# ICM-20948-Pico.net
KiCad netlist of a schematic drawn in EasyEDA Pro
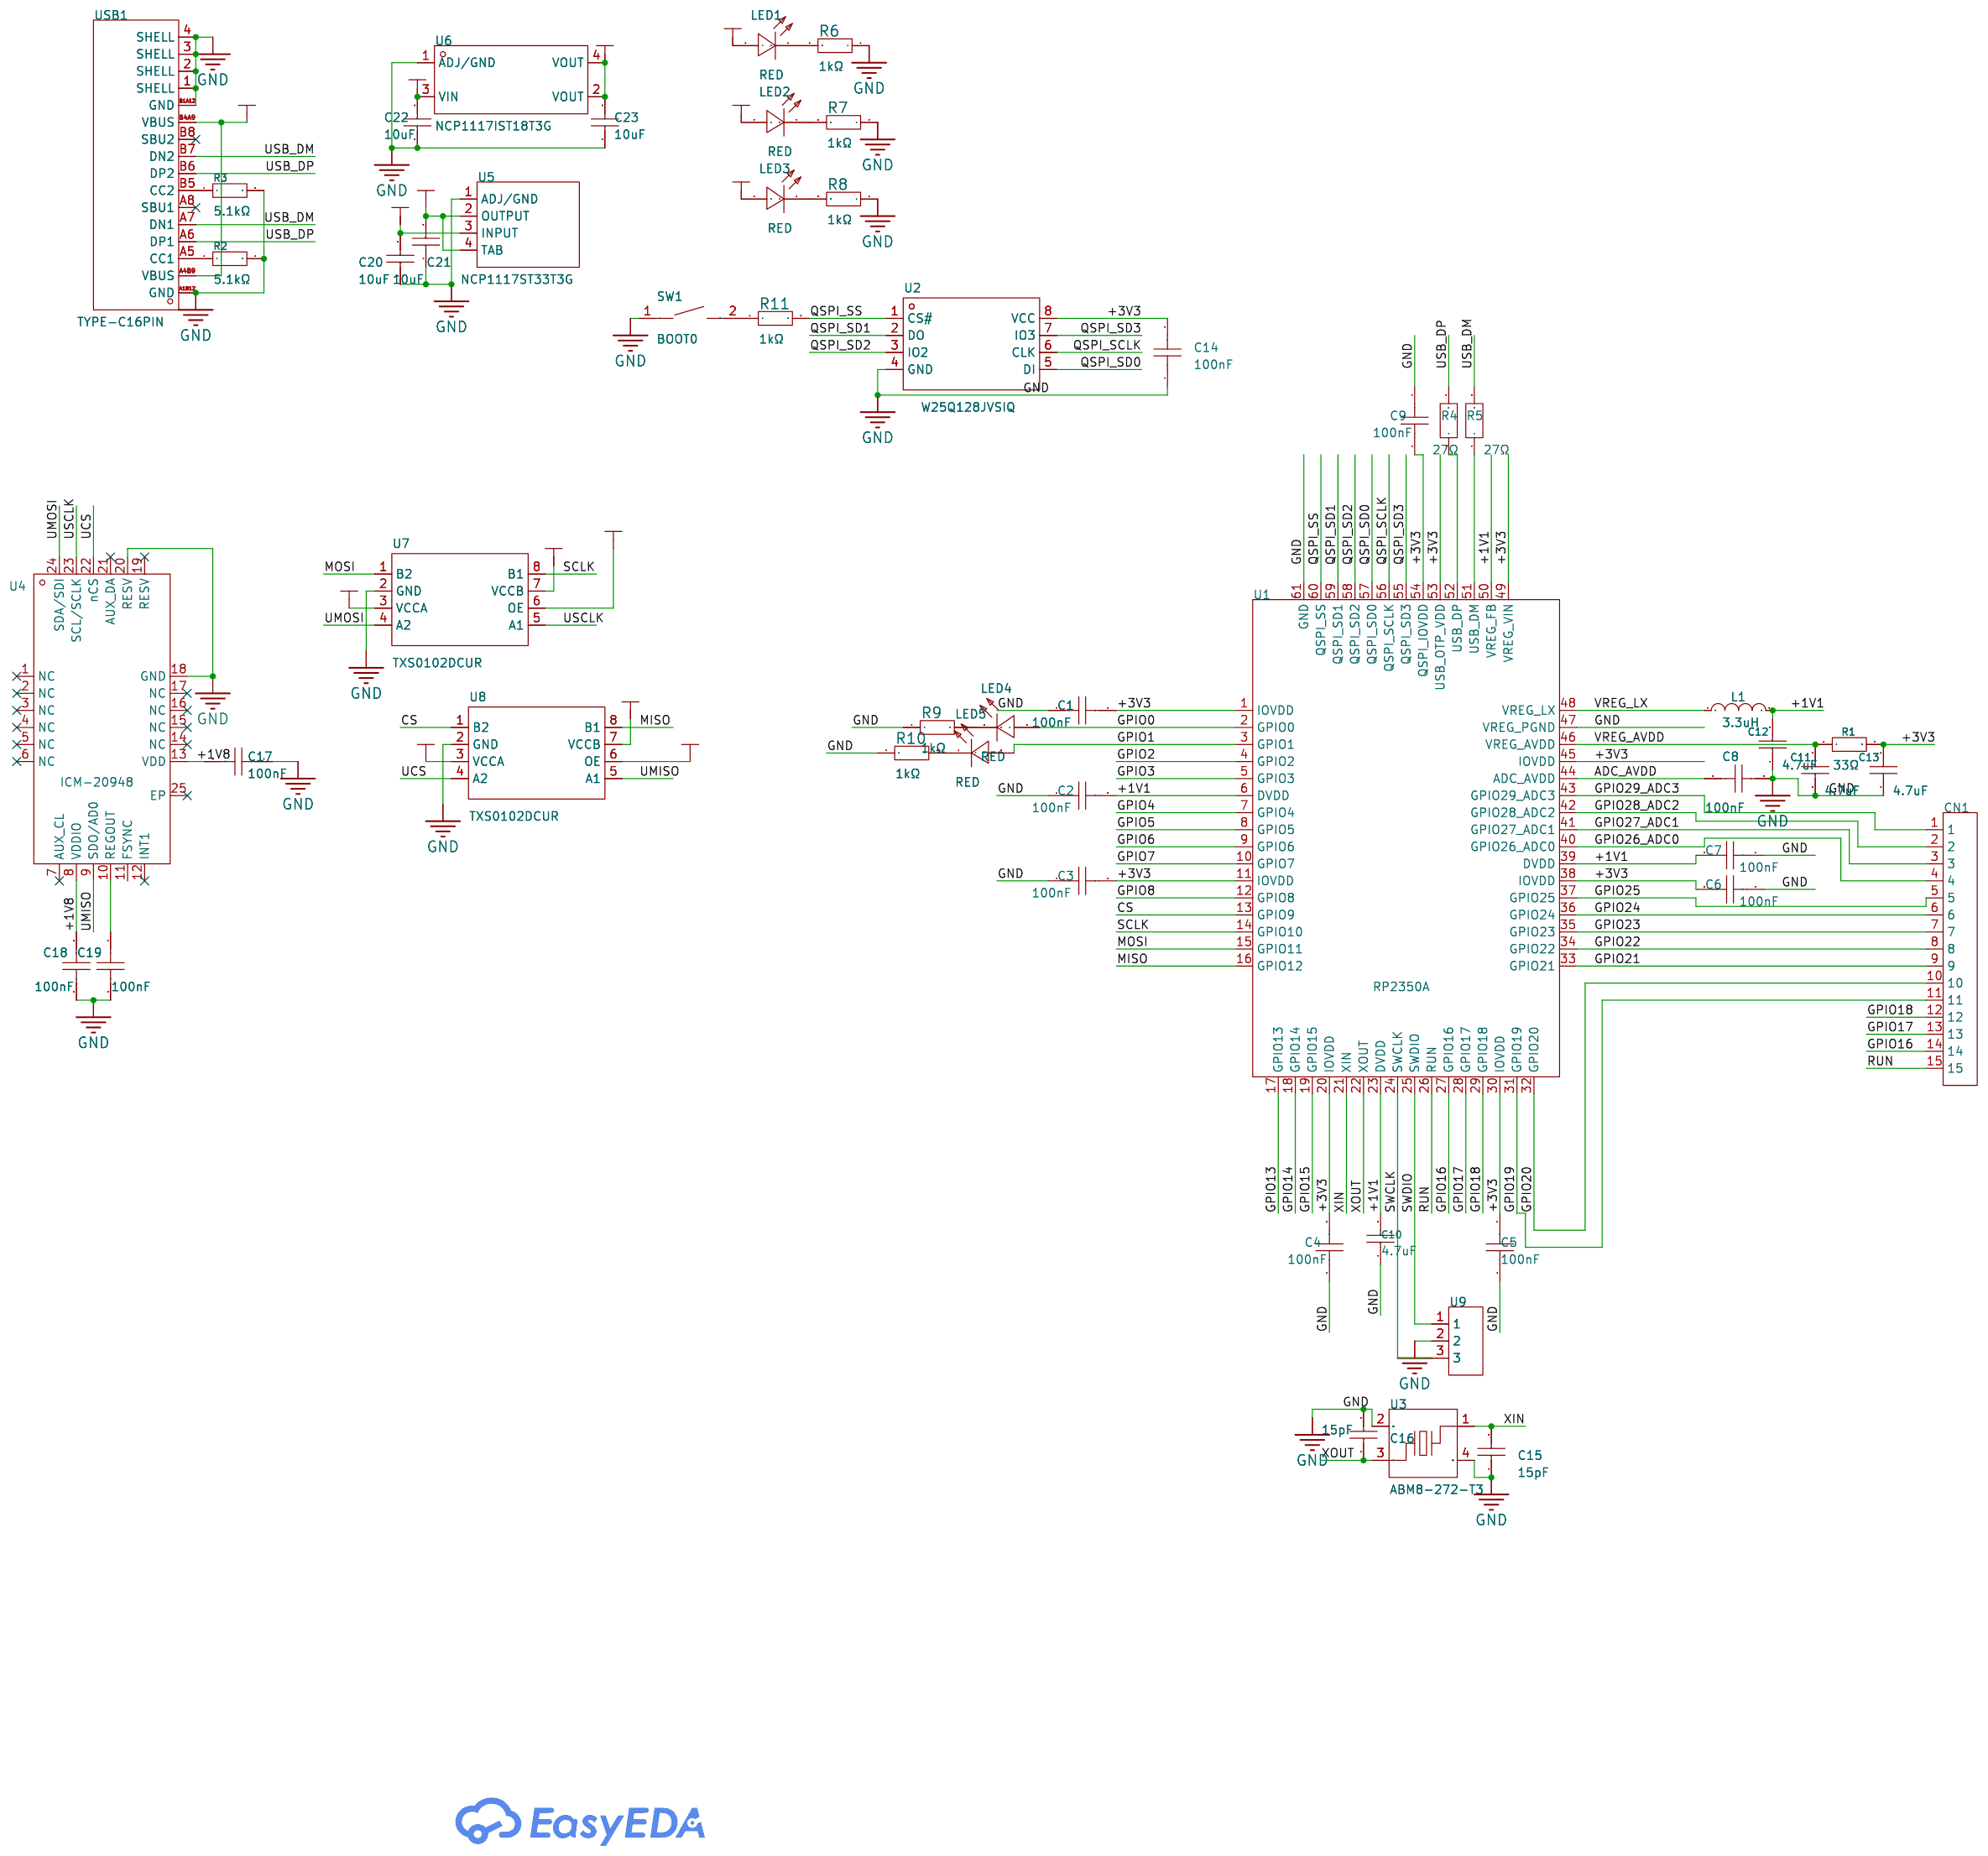
[diagram p0: schematic sheet]

(export (version "E")
  (design (tool "Eeschema 10.0.6"))
  (components
    (comp (ref "C1")
      (value "100nF")
      (footprint "easyedapro:C0402")
      (fields
        (field (name "Manufacturer Part") "CL05B104KO5NNNC")
        (field (name "Manufacturer") "SAMSUNG(三星)")
      )
      (libsource (lib "easyedapro") (part "CL05B104KO5NNNC"))
    )
    (comp (ref "C2")
      (value "100nF")
      (footprint "easyedapro:C0402")
      (fields
        (field (name "Manufacturer Part") "CL05B104KO5NNNC")
        (field (name "Manufacturer") "SAMSUNG(三星)")
      )
      (libsource (lib "easyedapro") (part "CL05B104KO5NNNC"))
    )
    (comp (ref "C3")
      (value "100nF")
      (footprint "easyedapro:C0402")
      (fields
        (field (name "Manufacturer Part") "CL05B104KO5NNNC")
        (field (name "Manufacturer") "SAMSUNG(三星)")
      )
      (libsource (lib "easyedapro") (part "CL05B104KO5NNNC"))
    )
    (comp (ref "C4")
      (value "100nF")
      (footprint "easyedapro:C0402")
      (fields
        (field (name "Manufacturer Part") "CL05B104KO5NNNC")
        (field (name "Manufacturer") "SAMSUNG(三星)")
      )
      (libsource (lib "easyedapro") (part "CL05B104KO5NNNC"))
    )
    (comp (ref "C5")
      (value "100nF")
      (footprint "easyedapro:C0402")
      (fields
        (field (name "Manufacturer Part") "CL05B104KO5NNNC")
        (field (name "Manufacturer") "SAMSUNG(三星)")
      )
      (libsource (lib "easyedapro") (part "CL05B104KO5NNNC"))
    )
    (comp (ref "C6")
      (value "100nF")
      (footprint "easyedapro:C0402")
      (fields
        (field (name "Manufacturer Part") "CL05B104KO5NNNC")
        (field (name "Manufacturer") "SAMSUNG(三星)")
      )
      (libsource (lib "easyedapro") (part "CL05B104KO5NNNC"))
    )
    (comp (ref "C7")
      (value "100nF")
      (footprint "easyedapro:C0402")
      (fields
        (field (name "Manufacturer Part") "CL05B104KO5NNNC")
        (field (name "Manufacturer") "SAMSUNG(三星)")
      )
      (libsource (lib "easyedapro") (part "CL05B104KO5NNNC"))
    )
    (comp (ref "C8")
      (value "100nF")
      (footprint "easyedapro:C0402")
      (fields
        (field (name "Manufacturer Part") "CL05B104KO5NNNC")
        (field (name "Manufacturer") "SAMSUNG(三星)")
      )
      (libsource (lib "easyedapro") (part "CL05B104KO5NNNC"))
    )
    (comp (ref "C9")
      (value "100nF")
      (footprint "easyedapro:C0402")
      (fields
        (field (name "Manufacturer Part") "CL05B104KO5NNNC")
        (field (name "Manufacturer") "SAMSUNG(三星)")
      )
      (libsource (lib "easyedapro") (part "CL05B104KO5NNNC"))
    )
    (comp (ref "C10")
      (value "4.7uF")
      (footprint "easyedapro:C0402")
      (fields
        (field (name "Manufacturer Part") "CL05A475MP5NRNC")
        (field (name "Manufacturer") "SAMSUNG(三星)")
      )
      (libsource (lib "easyedapro") (part "CL05A475MP5NRNC"))
    )
    (comp (ref "C11")
      (value "4.7uF")
      (footprint "easyedapro:C0402")
      (fields
        (field (name "Manufacturer Part") "CL05A475MP5NRNC")
        (field (name "Manufacturer") "SAMSUNG(三星)")
      )
      (libsource (lib "easyedapro") (part "CL05A475MP5NRNC"))
    )
    (comp (ref "C12")
      (value "4.7uF")
      (footprint "easyedapro:C0402")
      (fields
        (field (name "Manufacturer Part") "CL05A475MP5NRNC")
        (field (name "Manufacturer") "SAMSUNG(三星)")
      )
      (libsource (lib "easyedapro") (part "CL05A475MP5NRNC"))
    )
    (comp (ref "C13")
      (value "4.7uF")
      (footprint "easyedapro:C0402")
      (fields
        (field (name "Manufacturer Part") "CL05A475MP5NRNC")
        (field (name "Manufacturer") "SAMSUNG(三星)")
      )
      (libsource (lib "easyedapro") (part "CL05A475MP5NRNC"))
    )
    (comp (ref "C14")
      (value "100nF")
      (footprint "easyedapro:C0402")
      (fields
        (field (name "Manufacturer Part") "CL05B104KO5NNNC")
        (field (name "Manufacturer") "SAMSUNG(三星)")
      )
      (libsource (lib "easyedapro") (part "CL05B104KO5NNNC"))
    )
    (comp (ref "C15")
      (value "15pF")
      (footprint "easyedapro:C0402")
      (fields (field (name "Manufacturer Part") "0402CG150J500NT") (field (name "Manufacturer") "FH(风华)"))
      (libsource (lib "easyedapro") (part "0402CG150J500NT"))
    )
    (comp (ref "C16")
      (value "15pF")
      (footprint "easyedapro:C0402")
      (fields (field (name "Manufacturer Part") "0402CG150J500NT") (field (name "Manufacturer") "FH(风华)"))
      (libsource (lib "easyedapro") (part "0402CG150J500NT"))
    )
    (comp (ref "C17")
      (value "100nF")
      (footprint "easyedapro:C0402")
      (fields
        (field (name "Manufacturer Part") "CL05B104KO5NNNC")
        (field (name "Manufacturer") "SAMSUNG(三星)")
      )
      (libsource (lib "easyedapro") (part "CL05B104KO5NNNC"))
    )
    (comp (ref "C18")
      (value "100nF")
      (footprint "easyedapro:C0402")
      (fields
        (field (name "Manufacturer Part") "CL05B104KO5NNNC")
        (field (name "Manufacturer") "SAMSUNG(三星)")
      )
      (libsource (lib "easyedapro") (part "CL05B104KO5NNNC"))
    )
    (comp (ref "C19")
      (value "100nF")
      (footprint "easyedapro:C0402")
      (fields
        (field (name "Manufacturer Part") "CL05B104KO5NNNC")
        (field (name "Manufacturer") "SAMSUNG(三星)")
      )
      (libsource (lib "easyedapro") (part "CL05B104KO5NNNC"))
    )
    (comp (ref "C20")
      (value "10uF")
      (footprint "easyedapro:C0402")
      (fields
        (field (name "Manufacturer Part") "CL05A106MQ5NUNC")
        (field (name "Manufacturer") "SAMSUNG(三星)")
      )
      (libsource (lib "easyedapro") (part "CL05A106MQ5NUNC"))
    )
    (comp (ref "C21")
      (value "10uF")
      (footprint "easyedapro:C0402")
      (fields
        (field (name "Manufacturer Part") "CL05A106MQ5NUNC")
        (field (name "Manufacturer") "SAMSUNG(三星)")
      )
      (libsource (lib "easyedapro") (part "CL05A106MQ5NUNC"))
    )
    (comp (ref "C22")
      (value "10uF")
      (footprint "easyedapro:C0402")
      (fields
        (field (name "Manufacturer Part") "CL05A106MQ5NUNC")
        (field (name "Manufacturer") "SAMSUNG(三星)")
      )
      (libsource (lib "easyedapro") (part "CL05A106MQ5NUNC"))
    )
    (comp (ref "C23")
      (value "10uF")
      (footprint "easyedapro:C0402")
      (fields
        (field (name "Manufacturer Part") "CL05A106MQ5NUNC")
        (field (name "Manufacturer") "SAMSUNG(三星)")
      )
      (libsource (lib "easyedapro") (part "CL05A106MQ5NUNC"))
    )
    (comp (ref "CN1")
      (value "排母插针1X15P")
      (footprint "easyedapro:CONN-TH_15P-L38.5-W2.4-P2.54")
      (libsource (lib "easyedapro") (part "排母插针1X15P"))
    )
    (comp (ref "L1")
      (value "3.3uH")
      (footprint "easyedapro:IND-SMD_L2.0-W1.6_AOTA-B201610S3R3-101-T")
      (fields (field (name "Manufacturer") "ABRACON"))
      (libsource (lib "easyedapro") (part "AOTA-B201610S3R3-101-T"))
    )
    (comp (ref "LED1")
      (value "RED")
      (footprint "easyedapro:LED0603-RD")
      (fields (field (name "Manufacturer") "KENTO"))
      (libsource (lib "easyedapro") (part "KT-0603R"))
    )
    (comp (ref "LED2")
      (value "RED")
      (footprint "easyedapro:LED0603-RD")
      (fields (field (name "Manufacturer") "KENTO"))
      (libsource (lib "easyedapro") (part "KT-0603R"))
    )
    (comp (ref "LED3")
      (value "RED")
      (footprint "easyedapro:LED0603-RD")
      (fields (field (name "Manufacturer") "KENTO"))
      (libsource (lib "easyedapro") (part "KT-0603R"))
    )
    (comp (ref "LED4")
      (value "RED")
      (footprint "easyedapro:LED0603-RD")
      (fields (field (name "Manufacturer") "KENTO"))
      (libsource (lib "easyedapro") (part "KT-0603R"))
    )
    (comp (ref "LED5")
      (value "RED")
      (footprint "easyedapro:LED0603-RD")
      (fields (field (name "Manufacturer") "KENTO"))
      (libsource (lib "easyedapro") (part "KT-0603R"))
    )
    (comp (ref "R1")
      (value "33Ω")
      (footprint "easyedapro:R0402")
      (fields
        (field (name "Manufacturer Part") "0402WGF330JTCE")
        (field (name "Manufacturer") "UNI-ROYAL(厚声)")
      )
      (libsource (lib "easyedapro") (part "0402WGF330JTCE"))
    )
    (comp (ref "R2")
      (value "5.1kΩ")
      (footprint "easyedapro:R0402")
      (fields
        (field (name "Manufacturer Part") "0402WGF5101TCE")
        (field (name "Manufacturer") "UNI-ROYAL(厚声)")
      )
      (libsource (lib "easyedapro") (part "0402WGF5101TCE"))
    )
    (comp (ref "R3")
      (value "5.1kΩ")
      (footprint "easyedapro:R0402")
      (fields
        (field (name "Manufacturer Part") "0402WGF5101TCE")
        (field (name "Manufacturer") "UNI-ROYAL(厚声)")
      )
      (libsource (lib "easyedapro") (part "0402WGF5101TCE"))
    )
    (comp (ref "R4")
      (value "27Ω")
      (footprint "easyedapro:R0402")
      (fields (field (name "Manufacturer Part") "WR04X270JTL") (field (name "Manufacturer") "Walsin(华新科)"))
      (libsource (lib "easyedapro") (part "WR04X270 JTL"))
    )
    (comp (ref "R5")
      (value "27Ω")
      (footprint "easyedapro:R0402")
      (fields (field (name "Manufacturer Part") "WR04X270JTL") (field (name "Manufacturer") "Walsin(华新科)"))
      (libsource (lib "easyedapro") (part "WR04X270 JTL"))
    )
    (comp (ref "R6")
      (value "1kΩ")
      (footprint "easyedapro:R0402")
      (fields
        (field (name "Manufacturer Part") "0402WGF1001TCE")
        (field (name "Manufacturer") "UNI-ROYAL(厚声)")
      )
      (libsource (lib "easyedapro") (part "0402WGF1001TCE"))
    )
    (comp (ref "R7")
      (value "1kΩ")
      (footprint "easyedapro:R0402")
      (fields
        (field (name "Manufacturer Part") "0402WGF1001TCE")
        (field (name "Manufacturer") "UNI-ROYAL(厚声)")
      )
      (libsource (lib "easyedapro") (part "0402WGF1001TCE"))
    )
    (comp (ref "R8")
      (value "1kΩ")
      (footprint "easyedapro:R0402")
      (fields
        (field (name "Manufacturer Part") "0402WGF1001TCE")
        (field (name "Manufacturer") "UNI-ROYAL(厚声)")
      )
      (libsource (lib "easyedapro") (part "0402WGF1001TCE"))
    )
    (comp (ref "R9")
      (value "1kΩ")
      (footprint "easyedapro:R0402")
      (fields
        (field (name "Manufacturer Part") "0402WGF1001TCE")
        (field (name "Manufacturer") "UNI-ROYAL(厚声)")
      )
      (libsource (lib "easyedapro") (part "0402WGF1001TCE"))
    )
    (comp (ref "R10")
      (value "1kΩ")
      (footprint "easyedapro:R0402")
      (fields
        (field (name "Manufacturer Part") "0402WGF1001TCE")
        (field (name "Manufacturer") "UNI-ROYAL(厚声)")
      )
      (libsource (lib "easyedapro") (part "0402WGF1001TCE"))
    )
    (comp (ref "R11")
      (value "1kΩ")
      (footprint "easyedapro:R0402")
      (fields
        (field (name "Manufacturer Part") "0402WGF1001TCE")
        (field (name "Manufacturer") "UNI-ROYAL(厚声)")
      )
      (libsource (lib "easyedapro") (part "0402WGF1001TCE"))
    )
    (comp (ref "SW1")
      (value "BOOT0")
      (footprint "easyedapro:SW-SMD_L3.9-W3.0-P4.45")
      (fields (field (name "Manufacturer") "XUNPU(讯普)"))
      (libsource (lib "easyedapro") (part "TS-1088-AR02016"))
    )
    (comp (ref "U1")
      (value "RP2350A")
      (footprint "easyedapro:QFN-60_L7.0-W7.0-P0.40-TL-EP3.4")
      (fields (field (name "Manufacturer") "Raspberry Pi(树莓派)"))
      (libsource (lib "easyedapro") (part "RP2350A_C42411118"))
    )
    (comp (ref "U2")
      (value "W25Q128JVSIQ")
      (footprint "easyedapro:SOIC-8_L5.3-W5.3-P1.27-LS8.0-BL")
      (fields (field (name "Manufacturer") "WINBOND(华邦)"))
      (libsource (lib "easyedapro") (part "W25Q128JVSIQTR"))
    )
    (comp (ref "U3")
      (value "ABM8-272-T3")
      (footprint "easyedapro:CRYSTAL-SMD_4P-L3.2-W2.5-BL")
      (fields (field (name "Manufacturer") "ABRACON"))
      (libsource (lib "easyedapro") (part "ABM8-272-T3_C20625731"))
    )
    (comp (ref "U4")
      (value "ICM-20948")
      (footprint "easyedapro:QFN-24_L3.0-W3.0-P0.40-BL-EP")
      (fields (field (name "Manufacturer") "TDK InvenSense(应美盛)"))
      (libsource (lib "easyedapro") (part "ICM-20948"))
    )
    (comp (ref "U5")
      (value "NCP1117ST33T3G")
      (footprint "easyedapro:SOT-223-3_L6.5-W3.4-P2.30-LS7.0-BR")
      (fields (field (name "Manufacturer") "onsemi(安森美)"))
      (libsource (lib "easyedapro") (part "NCP1117ST33T3G"))
    )
    (comp (ref "U6")
      (value "NCP1117IST18T3G")
      (footprint "easyedapro:SOT-223_L6.5-W3.5-P2.30-LS7.0-BR")
      (fields (field (name "Manufacturer") "onsemi(安森美)"))
      (libsource (lib "easyedapro") (part "NCP1117IST18T3G"))
    )
    (comp (ref "U7")
      (value "TXS0102DCUR")
      (footprint "easyedapro:VSON8_L2.0-W2.3-P0.50-LS3.1-BL")
      (fields (field (name "Manufacturer") "TI(德州仪器)"))
      (libsource (lib "easyedapro") (part "TXS0102DCUR"))
    )
    (comp (ref "U8")
      (value "TXS0102DCUR")
      (footprint "easyedapro:VSON8_L2.0-W2.3-P0.50-LS3.1-BL")
      (fields (field (name "Manufacturer") "TI(德州仪器)"))
      (libsource (lib "easyedapro") (part "TXS0102DCUR"))
    )
    (comp (ref "U9")
      (value "HB-PH3-25413PB2GOP")
      (footprint "easyedapro:HDR-TH_3P-P2.54-V-M")
      (fields (field (name "Manufacturer") "HANBO(汉博)"))
      (libsource (lib "easyedapro") (part "HB-PH3-25413PB2GOP"))
    )
    (comp (ref "USB1")
      (value "TYPE-C16PIN")
      (footprint "easyedapro:USB-C-SMD_TYPE-C16PIN")
      (fields (field (name "Manufacturer") "SHOU HAN(首韩)"))
      (libsource (lib "easyedapro") (part "TYPE-C16PIN"))
    )
  )
  (nets
    (net (code "1") (name "+1V8") (class "Default")
      (node (ref "C17") (pin "2") (pinfunction "2_2") (pintype "unspecified"))
      (node (ref "C18") (pin "1") (pinfunction "1_1") (pintype "unspecified"))
      (node (ref "C23") (pin "2") (pinfunction "2_2") (pintype "input"))
      (node (ref "LED3") (pin "2") (pinfunction "A_2") (pintype "unspecified"))
      (node (ref "U4") (pin "13") (pinfunction "VDD_13") (pintype "unspecified"))
      (node (ref "U4") (pin "8") (pinfunction "VDDIO_8") (pintype "unspecified"))
      (node (ref "U6") (pin "2") (pinfunction "VOUT_2") (pintype "unspecified"))
      (node (ref "U6") (pin "4") (pinfunction "VOUT_4") (pintype "unspecified"))
      (node (ref "U7") (pin "3") (pinfunction "VCCA_3") (pintype "unspecified"))
      (node (ref "U7") (pin "6") (pinfunction "OE_6") (pintype "unspecified"))
      (node (ref "U8") (pin "3") (pinfunction "VCCA_3") (pintype "unspecified"))
      (node (ref "U8") (pin "6") (pinfunction "OE_6") (pintype "unspecified"))
    )
    (net (code "2") (name "+3V3") (class "Default")
      (node (ref "C1") (pin "2") (pinfunction "2_2") (pintype "unspecified"))
      (node (ref "C13") (pin "2") (pinfunction "2_2") (pintype "input"))
      (node (ref "C14") (pin "2") (pinfunction "2_2") (pintype "unspecified"))
      (node (ref "C21") (pin "2") (pinfunction "2_2") (pintype "input"))
      (node (ref "C3") (pin "2") (pinfunction "2_2") (pintype "unspecified"))
      (node (ref "C4") (pin "2") (pinfunction "2_2") (pintype "unspecified"))
      (node (ref "C5") (pin "2") (pinfunction "2_2") (pintype "unspecified"))
      (node (ref "C6") (pin "2") (pinfunction "2_2") (pintype "unspecified"))
      (node (ref "C9") (pin "2") (pinfunction "2_2") (pintype "unspecified"))
      (node (ref "LED2") (pin "2") (pinfunction "A_2") (pintype "unspecified"))
      (node (ref "R1") (pin "2") (pinfunction "2_2") (pintype "input"))
      (node (ref "U1") (pin "1") (pinfunction "IOVDD_1") (pintype "unspecified"))
      (node (ref "U1") (pin "11") (pinfunction "IOVDD_11") (pintype "unspecified"))
      (node (ref "U1") (pin "20") (pinfunction "IOVDD_20") (pintype "unspecified"))
      (node (ref "U1") (pin "30") (pinfunction "IOVDD_30") (pintype "unspecified"))
      (node (ref "U1") (pin "38") (pinfunction "IOVDD_38") (pintype "unspecified"))
      (node (ref "U1") (pin "45") (pinfunction "IOVDD_45") (pintype "unspecified"))
      (node (ref "U1") (pin "49") (pinfunction "VREG_VIN_49") (pintype "unspecified"))
      (node (ref "U1") (pin "53") (pinfunction "USB_OTP_VDD_53") (pintype "unspecified"))
      (node (ref "U1") (pin "54") (pinfunction "QSPI_IOVDD_54") (pintype "unspecified"))
      (node (ref "U2") (pin "8") (pinfunction "VCC_8") (pintype "unspecified"))
      (node (ref "U5") (pin "2") (pinfunction "OUTPUT_2") (pintype "unspecified"))
      (node (ref "U5") (pin "4") (pinfunction "TAB_4") (pintype "unspecified"))
      (node (ref "U7") (pin "7") (pinfunction "VCCB_7") (pintype "unspecified"))
      (node (ref "U8") (pin "7") (pinfunction "VCCB_7") (pintype "unspecified"))
    )
    (net (code "3") (name "/+1V1") (class "Default")
      (node (ref "C10") (pin "2") (pinfunction "2_2") (pintype "input"))
      (node (ref "C12") (pin "2") (pinfunction "2_2") (pintype "input"))
      (node (ref "C2") (pin "2") (pinfunction "2_2") (pintype "unspecified"))
      (node (ref "C7") (pin "2") (pinfunction "2_2") (pintype "unspecified"))
      (node (ref "L1") (pin "2") (pinfunction "2_2") (pintype "unspecified"))
      (node (ref "U1") (pin "23") (pinfunction "DVDD_23") (pintype "unspecified"))
      (node (ref "U1") (pin "39") (pinfunction "DVDD_39") (pintype "unspecified"))
      (node (ref "U1") (pin "50") (pinfunction "VREG_FB_50") (pintype "unspecified"))
      (node (ref "U1") (pin "6") (pinfunction "DVDD_6") (pintype "unspecified"))
    )
    (net (code "4") (name "/ADC_AVDD") (class "Default")
      (node (ref "C8") (pin "2") (pinfunction "2_2") (pintype "unspecified"))
      (node (ref "U1") (pin "44") (pinfunction "ADC_AVDD_44") (pintype "unspecified"))
    )
    (net (code "5") (name "/CS") (class "Default")
      (node (ref "U1") (pin "13") (pinfunction "GPIO9_13") (pintype "unspecified"))
      (node (ref "U8") (pin "1") (pinfunction "B2_1") (pintype "unspecified"))
    )
    (net (code "6") (name "/GPIO0") (class "Default")
      (node (ref "LED4") (pin "2") (pinfunction "A_2") (pintype "unspecified"))
      (node (ref "U1") (pin "2") (pinfunction "GPIO0_2") (pintype "unspecified"))
    )
    (net (code "7") (name "/GPIO1") (class "Default")
      (node (ref "LED5") (pin "2") (pinfunction "A_2") (pintype "unspecified"))
      (node (ref "U1") (pin "3") (pinfunction "GPIO1_3") (pintype "unspecified"))
    )
    (net (code "8") (name "/GPIO2") (class "Default")
      (node (ref "U1") (pin "4") (pinfunction "GPIO2_4") (pintype "unspecified"))
    )
    (net (code "9") (name "/GPIO3") (class "Default")
      (node (ref "U1") (pin "5") (pinfunction "GPIO3_5") (pintype "unspecified"))
    )
    (net (code "10") (name "/GPIO4") (class "Default")
      (node (ref "U1") (pin "7") (pinfunction "GPIO4_7") (pintype "unspecified"))
    )
    (net (code "11") (name "/GPIO5") (class "Default")
      (node (ref "U1") (pin "8") (pinfunction "GPIO5_8") (pintype "unspecified"))
    )
    (net (code "12") (name "/GPIO6") (class "Default")
      (node (ref "U1") (pin "9") (pinfunction "GPIO6_9") (pintype "unspecified"))
    )
    (net (code "13") (name "/GPIO7") (class "Default")
      (node (ref "U1") (pin "10") (pinfunction "GPIO7_10") (pintype "unspecified"))
    )
    (net (code "14") (name "/GPIO8") (class "Default")
      (node (ref "U1") (pin "12") (pinfunction "GPIO8_12") (pintype "unspecified"))
    )
    (net (code "15") (name "/GPIO13") (class "Default")
      (node (ref "U1") (pin "17") (pinfunction "GPIO13_17") (pintype "unspecified"))
    )
    (net (code "16") (name "/GPIO14") (class "Default")
      (node (ref "U1") (pin "18") (pinfunction "GPIO14_18") (pintype "unspecified"))
    )
    (net (code "17") (name "/GPIO15") (class "Default")
      (node (ref "U1") (pin "19") (pinfunction "GPIO15_19") (pintype "unspecified"))
    )
    (net (code "18") (name "/GPIO16") (class "Default")
      (node (ref "CN1") (pin "14") (pinfunction "14_14") (pintype "unspecified"))
      (node (ref "U1") (pin "27") (pinfunction "GPIO16_27") (pintype "unspecified"))
    )
    (net (code "19") (name "/GPIO17") (class "Default")
      (node (ref "CN1") (pin "13") (pinfunction "13_13") (pintype "unspecified"))
      (node (ref "U1") (pin "28") (pinfunction "GPIO17_28") (pintype "unspecified"))
    )
    (net (code "20") (name "/GPIO18") (class "Default")
      (node (ref "CN1") (pin "12") (pinfunction "12_12") (pintype "unspecified"))
      (node (ref "U1") (pin "29") (pinfunction "GPIO18_29") (pintype "unspecified"))
    )
    (net (code "21") (name "/GPIO19") (class "Default")
      (node (ref "CN1") (pin "11") (pinfunction "11_11") (pintype "unspecified"))
      (node (ref "U1") (pin "31") (pinfunction "GPIO19_31") (pintype "unspecified"))
    )
    (net (code "22") (name "/GPIO20") (class "Default")
      (node (ref "CN1") (pin "10") (pinfunction "10_10") (pintype "unspecified"))
      (node (ref "U1") (pin "32") (pinfunction "GPIO20_32") (pintype "unspecified"))
    )
    (net (code "23") (name "/GPIO21") (class "Default")
      (node (ref "CN1") (pin "9") (pinfunction "9_9") (pintype "unspecified"))
      (node (ref "U1") (pin "33") (pinfunction "GPIO21_33") (pintype "unspecified"))
    )
    (net (code "24") (name "/GPIO22") (class "Default")
      (node (ref "CN1") (pin "8") (pinfunction "8_8") (pintype "unspecified"))
      (node (ref "U1") (pin "34") (pinfunction "GPIO22_34") (pintype "unspecified"))
    )
    (net (code "25") (name "/GPIO23") (class "Default")
      (node (ref "CN1") (pin "7") (pinfunction "7_7") (pintype "unspecified"))
      (node (ref "U1") (pin "35") (pinfunction "GPIO23_35") (pintype "unspecified"))
    )
    (net (code "26") (name "/GPIO24") (class "Default")
      (node (ref "CN1") (pin "6") (pinfunction "6_6") (pintype "unspecified"))
      (node (ref "U1") (pin "36") (pinfunction "GPIO24_36") (pintype "unspecified"))
    )
    (net (code "27") (name "/GPIO25") (class "Default")
      (node (ref "CN1") (pin "5") (pinfunction "5_5") (pintype "unspecified"))
      (node (ref "U1") (pin "37") (pinfunction "GPIO25_37") (pintype "unspecified"))
    )
    (net (code "28") (name "/GPIO26_ADC0") (class "Default")
      (node (ref "CN1") (pin "4") (pinfunction "4_4") (pintype "unspecified"))
      (node (ref "U1") (pin "40") (pinfunction "GPIO26_ADC0_40") (pintype "unspecified"))
    )
    (net (code "29") (name "/GPIO27_ADC1") (class "Default")
      (node (ref "CN1") (pin "3") (pinfunction "3_3") (pintype "unspecified"))
      (node (ref "U1") (pin "41") (pinfunction "GPIO27_ADC1_41") (pintype "unspecified"))
    )
    (net (code "30") (name "/GPIO28_ADC2") (class "Default")
      (node (ref "CN1") (pin "2") (pinfunction "2_2") (pintype "unspecified"))
      (node (ref "U1") (pin "42") (pinfunction "GPIO28_ADC2_42") (pintype "unspecified"))
    )
    (net (code "31") (name "/GPIO29_ADC3") (class "Default")
      (node (ref "CN1") (pin "1") (pinfunction "1_1") (pintype "unspecified"))
      (node (ref "U1") (pin "43") (pinfunction "GPIO29_ADC3_43") (pintype "unspecified"))
    )
    (net (code "32") (name "/MISO") (class "Default")
      (node (ref "U1") (pin "16") (pinfunction "GPIO12_16") (pintype "unspecified"))
      (node (ref "U8") (pin "8") (pinfunction "B1_8") (pintype "unspecified"))
    )
    (net (code "33") (name "/MOSI") (class "Default")
      (node (ref "U1") (pin "15") (pinfunction "GPIO11_15") (pintype "unspecified"))
      (node (ref "U7") (pin "1") (pinfunction "B2_1") (pintype "unspecified"))
    )
    (net (code "34") (name "/QSPI_SCLK") (class "Default")
      (node (ref "U1") (pin "56") (pinfunction "QSPI_SCLK_56") (pintype "unspecified"))
      (node (ref "U2") (pin "6") (pinfunction "CLK_6") (pintype "unspecified"))
    )
    (net (code "35") (name "/QSPI_SD0") (class "Default")
      (node (ref "U1") (pin "57") (pinfunction "QSPI_SD0_57") (pintype "unspecified"))
      (node (ref "U2") (pin "5") (pinfunction "DI_5") (pintype "unspecified"))
    )
    (net (code "36") (name "/QSPI_SD1") (class "Default")
      (node (ref "U1") (pin "59") (pinfunction "QSPI_SD1_59") (pintype "unspecified"))
      (node (ref "U2") (pin "2") (pinfunction "DO_2") (pintype "unspecified"))
    )
    (net (code "37") (name "/QSPI_SD2") (class "Default")
      (node (ref "U1") (pin "58") (pinfunction "QSPI_SD2_58") (pintype "unspecified"))
      (node (ref "U2") (pin "3") (pinfunction "IO2_3") (pintype "unspecified"))
    )
    (net (code "38") (name "/QSPI_SD3") (class "Default")
      (node (ref "U1") (pin "55") (pinfunction "QSPI_SD3_55") (pintype "unspecified"))
      (node (ref "U2") (pin "7") (pinfunction "IO3_7") (pintype "unspecified"))
    )
    (net (code "39") (name "/QSPI_SS") (class "Default")
      (node (ref "R11") (pin "2") (pinfunction "2_2") (pintype "input"))
      (node (ref "U1") (pin "60") (pinfunction "QSPI_SS_60") (pintype "unspecified"))
      (node (ref "U2") (pin "1") (pinfunction "CS#_1") (pintype "unspecified"))
    )
    (net (code "40") (name "/RUN") (class "Default")
      (node (ref "CN1") (pin "15") (pinfunction "15_15") (pintype "unspecified"))
      (node (ref "U1") (pin "26") (pinfunction "RUN_26") (pintype "unspecified"))
    )
    (net (code "41") (name "/SCLK") (class "Default")
      (node (ref "U1") (pin "14") (pinfunction "GPIO10_14") (pintype "unspecified"))
      (node (ref "U7") (pin "8") (pinfunction "B1_8") (pintype "unspecified"))
    )
    (net (code "42") (name "/SWCLK") (class "Default")
      (node (ref "U1") (pin "24") (pinfunction "SWCLK_24") (pintype "unspecified"))
      (node (ref "U9") (pin "3") (pinfunction "3_3") (pintype "unspecified"))
    )
    (net (code "43") (name "/SWDIO") (class "Default")
      (node (ref "U1") (pin "25") (pinfunction "SWDIO_25") (pintype "unspecified"))
      (node (ref "U9") (pin "1") (pinfunction "1_1") (pintype "unspecified"))
    )
    (net (code "44") (name "/UCS") (class "Default")
      (node (ref "U4") (pin "22") (pinfunction "nCS_22") (pintype "unspecified"))
      (node (ref "U8") (pin "4") (pinfunction "A2_4") (pintype "unspecified"))
    )
    (net (code "45") (name "/UMISO") (class "Default")
      (node (ref "U4") (pin "9") (pinfunction "SDO/AD0_9") (pintype "unspecified"))
      (node (ref "U8") (pin "5") (pinfunction "A1_5") (pintype "unspecified"))
    )
    (net (code "46") (name "/UMOSI") (class "Default")
      (node (ref "U4") (pin "24") (pinfunction "SDA/SDI_24") (pintype "unspecified"))
      (node (ref "U7") (pin "4") (pinfunction "A2_4") (pintype "unspecified"))
    )
    (net (code "47") (name "/USB_DM") (class "Default")
      (node (ref "R5") (pin "2") (pinfunction "2_2") (pintype "unspecified"))
      (node (ref "USB1") (pin "A7") (pinfunction "DN1_A7") (pintype "unspecified"))
      (node (ref "USB1") (pin "B7") (pinfunction "DN2_B7") (pintype "unspecified"))
    )
    (net (code "48") (name "/USB_DP") (class "Default")
      (node (ref "R4") (pin "2") (pinfunction "2_2") (pintype "unspecified"))
      (node (ref "USB1") (pin "A6") (pinfunction "DP1_A6") (pintype "unspecified"))
      (node (ref "USB1") (pin "B6") (pinfunction "DP2_B6") (pintype "unspecified"))
    )
    (net (code "49") (name "/USCLK") (class "Default")
      (node (ref "U4") (pin "23") (pinfunction "SCL/SCLK_23") (pintype "unspecified"))
      (node (ref "U7") (pin "5") (pinfunction "A1_5") (pintype "unspecified"))
    )
    (net (code "50") (name "/VREG_AVDD") (class "Default")
      (node (ref "C11") (pin "2") (pinfunction "2_2") (pintype "input"))
      (node (ref "R1") (pin "1") (pinfunction "1_1") (pintype "input"))
      (node (ref "U1") (pin "46") (pinfunction "VREG_AVDD_46") (pintype "unspecified"))
    )
    (net (code "51") (name "/VREG_LX") (class "Default")
      (node (ref "L1") (pin "1") (pinfunction "1_1") (pintype "unspecified"))
      (node (ref "U1") (pin "48") (pinfunction "VREG_LX_48") (pintype "unspecified"))
    )
    (net (code "52") (name "/XIN") (class "Default")
      (node (ref "C15") (pin "2") (pinfunction "2_2") (pintype "input"))
      (node (ref "U1") (pin "21") (pinfunction "XIN_21") (pintype "unspecified"))
      (node (ref "U3") (pin "1") (pinfunction "1_1") (pintype "input"))
    )
    (net (code "53") (name "/XOUT") (class "Default")
      (node (ref "C16") (pin "1") (pinfunction "1_1") (pintype "input"))
      (node (ref "U1") (pin "22") (pinfunction "XOUT_22") (pintype "unspecified"))
      (node (ref "U3") (pin "3") (pinfunction "3_3") (pintype "input"))
    )
    (net (code "54") (name "GND") (class "Default")
      (node (ref "C1") (pin "1") (pinfunction "1_1") (pintype "unspecified"))
      (node (ref "C10") (pin "1") (pinfunction "1_1") (pintype "input"))
      (node (ref "C11") (pin "1") (pinfunction "1_1") (pintype "input"))
      (node (ref "C12") (pin "1") (pinfunction "1_1") (pintype "input"))
      (node (ref "C13") (pin "1") (pinfunction "1_1") (pintype "input"))
      (node (ref "C14") (pin "1") (pinfunction "1_1") (pintype "unspecified"))
      (node (ref "C15") (pin "1") (pinfunction "1_1") (pintype "input"))
      (node (ref "C16") (pin "2") (pinfunction "2_2") (pintype "input"))
      (node (ref "C17") (pin "1") (pinfunction "1_1") (pintype "unspecified"))
      (node (ref "C18") (pin "2") (pinfunction "2_2") (pintype "unspecified"))
      (node (ref "C19") (pin "2") (pinfunction "2_2") (pintype "unspecified"))
      (node (ref "C2") (pin "1") (pinfunction "1_1") (pintype "unspecified"))
      (node (ref "C20") (pin "1") (pinfunction "1_1") (pintype "input"))
      (node (ref "C21") (pin "1") (pinfunction "1_1") (pintype "input"))
      (node (ref "C22") (pin "1") (pinfunction "1_1") (pintype "input"))
      (node (ref "C23") (pin "1") (pinfunction "1_1") (pintype "input"))
      (node (ref "C3") (pin "1") (pinfunction "1_1") (pintype "unspecified"))
      (node (ref "C4") (pin "1") (pinfunction "1_1") (pintype "unspecified"))
      (node (ref "C5") (pin "1") (pinfunction "1_1") (pintype "unspecified"))
      (node (ref "C6") (pin "1") (pinfunction "1_1") (pintype "unspecified"))
      (node (ref "C7") (pin "1") (pinfunction "1_1") (pintype "unspecified"))
      (node (ref "C8") (pin "1") (pinfunction "1_1") (pintype "unspecified"))
      (node (ref "C9") (pin "1") (pinfunction "1_1") (pintype "unspecified"))
      (node (ref "R10") (pin "1") (pinfunction "1_1") (pintype "input"))
      (node (ref "R2") (pin "2") (pinfunction "2_2") (pintype "input"))
      (node (ref "R3") (pin "2") (pinfunction "2_2") (pintype "input"))
      (node (ref "R6") (pin "1") (pinfunction "1_1") (pintype "input"))
      (node (ref "R7") (pin "1") (pinfunction "1_1") (pintype "input"))
      (node (ref "R8") (pin "1") (pinfunction "1_1") (pintype "input"))
      (node (ref "R9") (pin "1") (pinfunction "1_1") (pintype "input"))
      (node (ref "SW1") (pin "1") (pinfunction "1_1") (pintype "unspecified"))
      (node (ref "U1") (pin "47") (pinfunction "VREG_PGND_47") (pintype "unspecified"))
      (node (ref "U1") (pin "61") (pinfunction "GND_61") (pintype "unspecified"))
      (node (ref "U2") (pin "4") (pinfunction "GND_4") (pintype "unspecified"))
      (node (ref "U3") (pin "2") (pinfunction "GND_2") (pintype "input"))
      (node (ref "U3") (pin "4") (pinfunction "GND_4") (pintype "input"))
      (node (ref "U4") (pin "18") (pinfunction "GND_18") (pintype "unspecified"))
      (node (ref "U4") (pin "20") (pinfunction "RESV_20") (pintype "unspecified"))
      (node (ref "U5") (pin "1") (pinfunction "ADJ/GND_1") (pintype "unspecified"))
      (node (ref "U6") (pin "1") (pinfunction "ADJ/GND_1") (pintype "unspecified"))
      (node (ref "U7") (pin "2") (pinfunction "GND_2") (pintype "unspecified"))
      (node (ref "U8") (pin "2") (pinfunction "GND_2") (pintype "unspecified"))
      (node (ref "U9") (pin "2") (pinfunction "2_2") (pintype "unspecified"))
      (node (ref "USB1") (pin "1") (pinfunction "SHELL_1") (pintype "unspecified"))
      (node (ref "USB1") (pin "2") (pinfunction "SHELL_2") (pintype "unspecified"))
      (node (ref "USB1") (pin "3") (pinfunction "SHELL_3") (pintype "unspecified"))
      (node (ref "USB1") (pin "4") (pinfunction "SHELL_4") (pintype "unspecified"))
      (node (ref "USB1") (pin "A1B12") (pinfunction "GND_A1B12") (pintype "unspecified"))
      (node (ref "USB1") (pin "B1A12") (pinfunction "GND_B1A12") (pintype "unspecified"))
    )
    (net (code "55") (name "Net-(LED1-K)") (class "Default")
      (node (ref "LED1") (pin "1") (pinfunction "K_1") (pintype "unspecified"))
      (node (ref "R6") (pin "2") (pinfunction "2_2") (pintype "input"))
    )
    (net (code "56") (name "Net-(LED2-K)") (class "Default")
      (node (ref "LED2") (pin "1") (pinfunction "K_1") (pintype "unspecified"))
      (node (ref "R7") (pin "2") (pinfunction "2_2") (pintype "input"))
    )
    (net (code "57") (name "Net-(LED3-K)") (class "Default")
      (node (ref "LED3") (pin "1") (pinfunction "K_1") (pintype "unspecified"))
      (node (ref "R8") (pin "2") (pinfunction "2_2") (pintype "input"))
    )
    (net (code "58") (name "Net-(LED4-K)") (class "Default")
      (node (ref "LED4") (pin "1") (pinfunction "K_1") (pintype "unspecified"))
      (node (ref "R9") (pin "2") (pinfunction "2_2") (pintype "input"))
    )
    (net (code "59") (name "Net-(LED5-K)") (class "Default")
      (node (ref "LED5") (pin "1") (pinfunction "K_1") (pintype "unspecified"))
      (node (ref "R10") (pin "2") (pinfunction "2_2") (pintype "input"))
    )
    (net (code "60") (name "Net-(R11-Pad1)") (class "Default")
      (node (ref "R11") (pin "1") (pinfunction "1_1") (pintype "input"))
      (node (ref "SW1") (pin "2") (pinfunction "2_2") (pintype "unspecified"))
    )
    (net (code "61") (name "Net-(U1-USB_DM)") (class "Default")
      (node (ref "R5") (pin "1") (pinfunction "1_1") (pintype "unspecified"))
      (node (ref "U1") (pin "51") (pinfunction "USB_DM_51") (pintype "unspecified"))
    )
    (net (code "62") (name "Net-(U1-USB_DP)") (class "Default")
      (node (ref "R4") (pin "1") (pinfunction "1_1") (pintype "unspecified"))
      (node (ref "U1") (pin "52") (pinfunction "USB_DP_52") (pintype "unspecified"))
    )
    (net (code "63") (name "Net-(U4-REGOUT)") (class "Default")
      (node (ref "C19") (pin "1") (pinfunction "1_1") (pintype "unspecified"))
      (node (ref "U4") (pin "10") (pinfunction "REGOUT_10") (pintype "unspecified"))
    )
    (net (code "64") (name "Net-(USB1-CC1)") (class "Default")
      (node (ref "R2") (pin "1") (pinfunction "1_1") (pintype "input"))
      (node (ref "USB1") (pin "A5") (pinfunction "CC1_A5") (pintype "unspecified"))
    )
    (net (code "65") (name "Net-(USB1-CC2)") (class "Default")
      (node (ref "R3") (pin "1") (pinfunction "1_1") (pintype "input"))
      (node (ref "USB1") (pin "B5") (pinfunction "CC2_B5") (pintype "unspecified"))
    )
    (net (code "66") (name "VBUS") (class "Default")
      (node (ref "C20") (pin "2") (pinfunction "2_2") (pintype "input"))
      (node (ref "C22") (pin "2") (pinfunction "2_2") (pintype "input"))
      (node (ref "LED1") (pin "2") (pinfunction "A_2") (pintype "unspecified"))
      (node (ref "U5") (pin "3") (pinfunction "INPUT_3") (pintype "unspecified"))
      (node (ref "U6") (pin "3") (pinfunction "VIN_3") (pintype "unspecified"))
      (node (ref "USB1") (pin "A4B9") (pinfunction "VBUS_A4B9") (pintype "unspecified"))
      (node (ref "USB1") (pin "B4A9") (pinfunction "VBUS_B4A9") (pintype "unspecified"))
    )
    (net (code "67") (name "unconnected-(U4-AUX_CL-Pad7)") (class "Default")
      (node (ref "U4") (pin "7") (pinfunction "AUX_CL_7") (pintype "unspecified+no_connect"))
    )
    (net (code "68") (name "unconnected-(U4-AUX_DA-Pad21)") (class "Default")
      (node (ref "U4") (pin "21") (pinfunction "AUX_DA_21") (pintype "unspecified+no_connect"))
    )
    (net (code "69") (name "unconnected-(U4-EP-Pad25)") (class "Default")
      (node (ref "U4") (pin "25") (pinfunction "EP_25") (pintype "unspecified+no_connect"))
    )
    (net (code "70") (name "unconnected-(U4-FSYNC-Pad11)") (class "Default")
      (node (ref "U4") (pin "11") (pinfunction "FSYNC_11") (pintype "unspecified"))
    )
    (net (code "71") (name "unconnected-(U4-INT1-Pad12)") (class "Default")
      (node (ref "U4") (pin "12") (pinfunction "INT1_12") (pintype "unspecified+no_connect"))
    )
    (net (code "72") (name "unconnected-(U4-NC-Pad1)") (class "Default")
      (node (ref "U4") (pin "1") (pinfunction "NC_1") (pintype "unspecified+no_connect"))
    )
    (net (code "73") (name "unconnected-(U4-NC-Pad2)") (class "Default")
      (node (ref "U4") (pin "2") (pinfunction "NC_2") (pintype "unspecified+no_connect"))
    )
    (net (code "74") (name "unconnected-(U4-NC-Pad3)") (class "Default")
      (node (ref "U4") (pin "3") (pinfunction "NC_3") (pintype "unspecified+no_connect"))
    )
    (net (code "75") (name "unconnected-(U4-NC-Pad4)") (class "Default")
      (node (ref "U4") (pin "4") (pinfunction "NC_4") (pintype "unspecified+no_connect"))
    )
    (net (code "76") (name "unconnected-(U4-NC-Pad5)") (class "Default")
      (node (ref "U4") (pin "5") (pinfunction "NC_5") (pintype "unspecified+no_connect"))
    )
    (net (code "77") (name "unconnected-(U4-NC-Pad6)") (class "Default")
      (node (ref "U4") (pin "6") (pinfunction "NC_6") (pintype "unspecified+no_connect"))
    )
    (net (code "78") (name "unconnected-(U4-NC-Pad14)") (class "Default")
      (node (ref "U4") (pin "14") (pinfunction "NC_14") (pintype "unspecified+no_connect"))
    )
    (net (code "79") (name "unconnected-(U4-NC-Pad15)") (class "Default")
      (node (ref "U4") (pin "15") (pinfunction "NC_15") (pintype "unspecified+no_connect"))
    )
    (net (code "80") (name "unconnected-(U4-NC-Pad16)") (class "Default")
      (node (ref "U4") (pin "16") (pinfunction "NC_16") (pintype "unspecified+no_connect"))
    )
    (net (code "81") (name "unconnected-(U4-NC-Pad17)") (class "Default")
      (node (ref "U4") (pin "17") (pinfunction "NC_17") (pintype "unspecified+no_connect"))
    )
    (net (code "82") (name "unconnected-(U4-RESV-Pad19)") (class "Default")
      (node (ref "U4") (pin "19") (pinfunction "RESV_19") (pintype "unspecified+no_connect"))
    )
    (net (code "83") (name "unconnected-(USB1-SBU1-PadA8)") (class "Default")
      (node (ref "USB1") (pin "A8") (pinfunction "SBU1_A8") (pintype "unspecified+no_connect"))
    )
    (net (code "84") (name "unconnected-(USB1-SBU2-PadB8)") (class "Default")
      (node (ref "USB1") (pin "B8") (pinfunction "SBU2_B8") (pintype "unspecified+no_connect"))
    )
  )
)
